# FilterControl_Schematic.net
KiCad netlist of a schematic drawn in Altium Designer
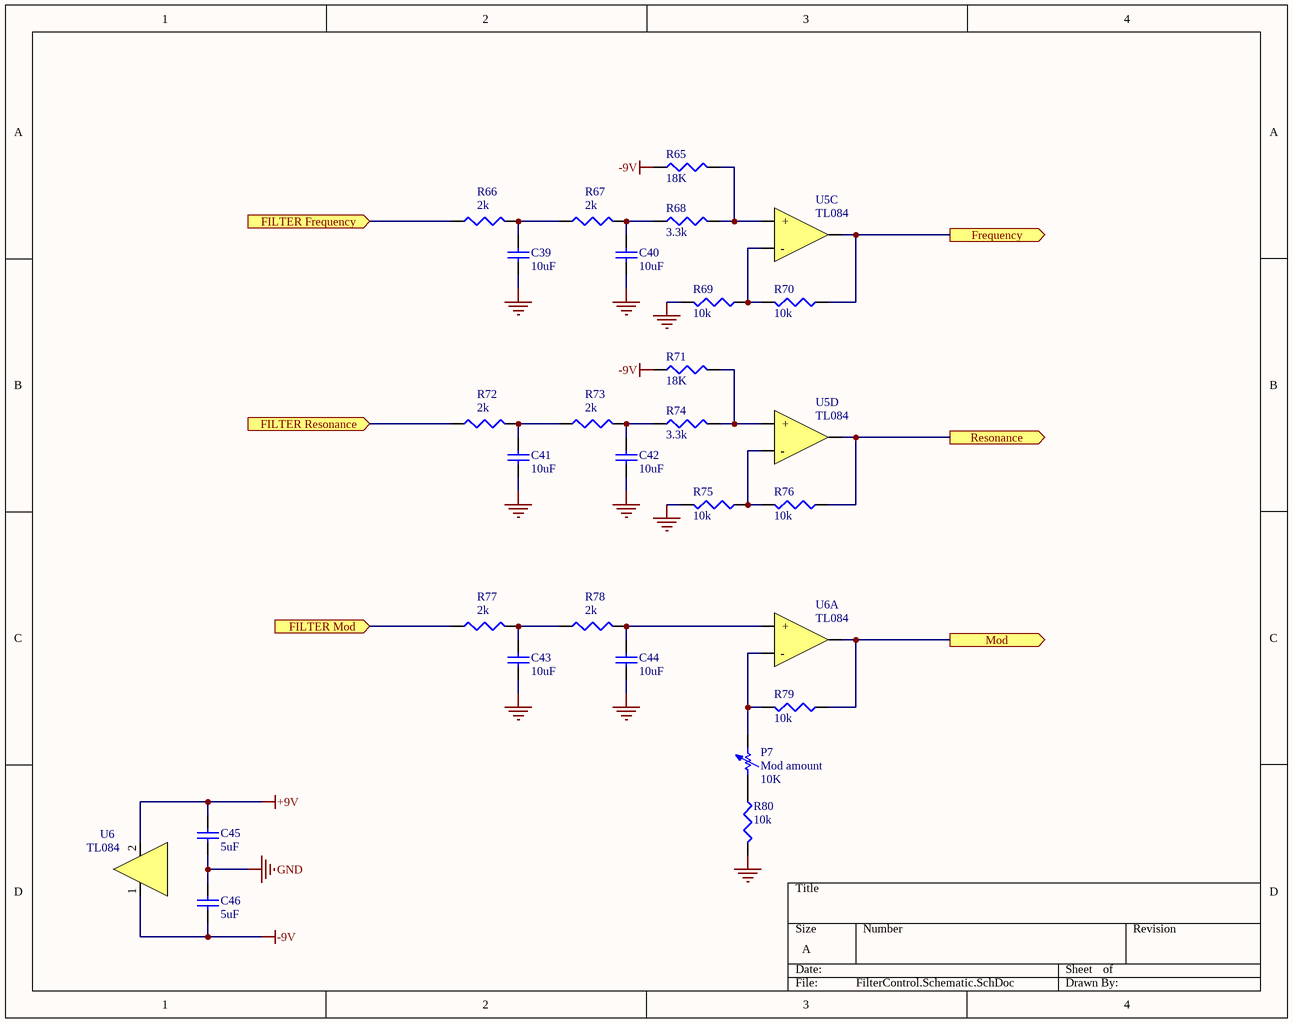
[diagram p0: FilterControl.Schematic.SchDoc]

(export (version "E")
  (design (tool "Eeschema 10.0.6"))
  (components
    (comp (ref "C39")
      (value "10uF")
      (footprint "CAPC1608N - cap")
      (description "Capacitor (Semiconductor SIM Model)")
      (fields (field (name "PUBLISHER") "Altium Limited"))
      (libsource (lib "Miscellaneous Devices") (part "Cap Semi"))
    )
    (comp (ref "C40")
      (value "10uF")
      (footprint "CAPC1608N - cap")
      (description "Capacitor (Semiconductor SIM Model)")
      (fields (field (name "PUBLISHER") "Altium Limited"))
      (libsource (lib "Miscellaneous Devices") (part "Cap Semi"))
    )
    (comp (ref "C41")
      (value "10uF")
      (footprint "CAPC1608N - cap")
      (description "Capacitor (Semiconductor SIM Model)")
      (fields (field (name "PUBLISHER") "Altium Limited"))
      (libsource (lib "Miscellaneous Devices") (part "Cap Semi"))
    )
    (comp (ref "C42")
      (value "10uF")
      (footprint "CAPC1608N - cap")
      (description "Capacitor (Semiconductor SIM Model)")
      (fields (field (name "PUBLISHER") "Altium Limited"))
      (libsource (lib "Miscellaneous Devices") (part "Cap Semi"))
    )
    (comp (ref "C43")
      (value "10uF")
      (footprint "CAPC1608N - cap")
      (description "Capacitor (Semiconductor SIM Model)")
      (fields (field (name "PUBLISHER") "Altium Limited"))
      (libsource (lib "Miscellaneous Devices") (part "Cap Semi"))
    )
    (comp (ref "C44")
      (value "10uF")
      (footprint "CAPC1608N - cap")
      (description "Capacitor (Semiconductor SIM Model)")
      (fields (field (name "PUBLISHER") "Altium Limited"))
      (libsource (lib "Miscellaneous Devices") (part "Cap Semi"))
    )
    (comp (ref "C45")
      (value "5uF")
      (footprint "CAPC1608N - cap")
      (description "Capacitor (Semiconductor SIM Model)")
      (fields (field (name "PUBLISHER") "Altium Limited"))
      (libsource (lib "Miscellaneous Devices") (part "Cap Semi"))
    )
    (comp (ref "C46")
      (value "5uF")
      (footprint "CAPC1608N - cap")
      (description "Capacitor (Semiconductor SIM Model)")
      (fields (field (name "PUBLISHER") "Altium Limited"))
      (libsource (lib "Miscellaneous Devices") (part "Cap Semi"))
    )
    (comp (ref "P7")
      (value "Mod amount")
      (footprint "CAPC1608N")
      (description "Variable Resistor")
      (fields (field (name "ALTIUM_VALUE") "10K") (field (name "PUBLISHER") "Altium Limited"))
      (libsource (lib "Miscellaneous Devices") (part "Res Adj1"))
    )
    (comp (ref "R65")
      (value "18K")
      (footprint "CAPC1608N")
      (description "Resistor")
      (fields (field (name "PUBLISHER") "Altium Limited"))
      (libsource (lib "Miscellaneous Devices") (part "Res3"))
    )
    (comp (ref "R66")
      (value "2k")
      (footprint "CAPC1608N")
      (description "Resistor")
      (fields (field (name "PUBLISHER") "Altium Limited"))
      (libsource (lib "Miscellaneous Devices") (part "Res3"))
    )
    (comp (ref "R67")
      (value "2k")
      (footprint "CAPC1608N")
      (description "Resistor")
      (fields (field (name "PUBLISHER") "Altium Limited"))
      (libsource (lib "Miscellaneous Devices") (part "Res3"))
    )
    (comp (ref "R68")
      (value "3.3k")
      (footprint "CAPC1608N")
      (description "Resistor")
      (fields (field (name "PUBLISHER") "Altium Limited"))
      (libsource (lib "Miscellaneous Devices") (part "Res3"))
    )
    (comp (ref "R69")
      (value "10k")
      (footprint "CAPC1608N")
      (description "Resistor")
      (fields (field (name "PUBLISHER") "Altium Limited"))
      (libsource (lib "Miscellaneous Devices") (part "Res3"))
    )
    (comp (ref "R70")
      (value "10k")
      (footprint "CAPC1608N")
      (description "Resistor")
      (fields (field (name "PUBLISHER") "Altium Limited"))
      (libsource (lib "Miscellaneous Devices") (part "Res3"))
    )
    (comp (ref "R71")
      (value "18K")
      (footprint "CAPC1608N")
      (description "Resistor")
      (fields (field (name "PUBLISHER") "Altium Limited"))
      (libsource (lib "Miscellaneous Devices") (part "Res3"))
    )
    (comp (ref "R72")
      (value "2k")
      (footprint "CAPC1608N")
      (description "Resistor")
      (fields (field (name "PUBLISHER") "Altium Limited"))
      (libsource (lib "Miscellaneous Devices") (part "Res3"))
    )
    (comp (ref "R73")
      (value "2k")
      (footprint "CAPC1608N")
      (description "Resistor")
      (fields (field (name "PUBLISHER") "Altium Limited"))
      (libsource (lib "Miscellaneous Devices") (part "Res3"))
    )
    (comp (ref "R74")
      (value "3.3k")
      (footprint "CAPC1608N")
      (description "Resistor")
      (fields (field (name "PUBLISHER") "Altium Limited"))
      (libsource (lib "Miscellaneous Devices") (part "Res3"))
    )
    (comp (ref "R75")
      (value "10k")
      (footprint "CAPC1608N")
      (description "Resistor")
      (fields (field (name "PUBLISHER") "Altium Limited"))
      (libsource (lib "Miscellaneous Devices") (part "Res3"))
    )
    (comp (ref "R76")
      (value "10k")
      (footprint "CAPC1608N")
      (description "Resistor")
      (fields (field (name "PUBLISHER") "Altium Limited"))
      (libsource (lib "Miscellaneous Devices") (part "Res3"))
    )
    (comp (ref "R77")
      (value "2k")
      (footprint "CAPC1608N")
      (description "Resistor")
      (fields (field (name "PUBLISHER") "Altium Limited"))
      (libsource (lib "Miscellaneous Devices") (part "Res3"))
    )
    (comp (ref "R78")
      (value "2k")
      (footprint "CAPC1608N")
      (description "Resistor")
      (fields (field (name "PUBLISHER") "Altium Limited"))
      (libsource (lib "Miscellaneous Devices") (part "Res3"))
    )
    (comp (ref "R79")
      (value "10k")
      (footprint "CAPC1608N")
      (description "Resistor")
      (fields (field (name "PUBLISHER") "Altium Limited"))
      (libsource (lib "Miscellaneous Devices") (part "Res3"))
    )
    (comp (ref "R80")
      (value "10k")
      (footprint "CAPC1608N")
      (description "Resistor")
      (fields (field (name "PUBLISHER") "Altium Limited"))
      (libsource (lib "Miscellaneous Devices") (part "Res3"))
    )
    (comp (ref "U5C")
      (value "TL084")
      (footprint "TL084 - 3pads")
      (libsource (lib "SynthyTwo.Components") (part "TL084"))
    )
    (comp (ref "U5D")
      (value "TL084")
      (footprint "TL084 - 3pads")
      (libsource (lib "SynthyTwo.Components") (part "TL084"))
    )
    (comp (ref "U6")
      (value "TL084")
      (footprint "TL084 - Alim")
      (libsource (lib "SynthyTwo.Components") (part "TL_CLEAN"))
    )
    (comp (ref "U6A")
      (value "TL084")
      (footprint "TL084 - 3pads")
      (libsource (lib "SynthyTwo.Components") (part "TL084"))
    )
  )
  (nets
    (net (code "1") (name "+9V") (class "Default")
      (node (ref "C45") (pin "1") (pinfunction "1_1") (pintype "passive"))
      (node (ref "U6") (pin "2") (pinfunction "VCC-_2") (pintype "passive"))
    )
    (net (code "2") (name "-9V") (class "Default")
      (node (ref "C46") (pin "2") (pinfunction "2_2") (pintype "passive"))
      (node (ref "R65") (pin "1") (pinfunction "1_1") (pintype "passive"))
      (node (ref "R71") (pin "1") (pinfunction "1_1") (pintype "passive"))
      (node (ref "U6") (pin "1") (pinfunction "VCC+_1") (pintype "passive"))
    )
    (net (code "3") (name "/FILTER Frequency") (class "Default")
      (node (ref "R66") (pin "1") (pinfunction "1_1") (pintype "passive"))
    )
    (net (code "4") (name "/FILTER Mod") (class "Default")
      (node (ref "R77") (pin "1") (pinfunction "1_1") (pintype "passive"))
    )
    (net (code "5") (name "/FILTER Resonance") (class "Default")
      (node (ref "R72") (pin "1") (pinfunction "1_1") (pintype "passive"))
    )
    (net (code "6") (name "/Frequency") (class "Default")
      (node (ref "R70") (pin "1") (pinfunction "1_1") (pintype "passive"))
      (node (ref "U5C") (pin "1") (pinfunction "OUT_1") (pintype "passive"))
    )
    (net (code "7") (name "/Mod") (class "Default")
      (node (ref "R79") (pin "1") (pinfunction "1_1") (pintype "passive"))
      (node (ref "U6A") (pin "1") (pinfunction "OUT_1") (pintype "passive"))
    )
    (net (code "8") (name "/Resonance") (class "Default")
      (node (ref "R76") (pin "1") (pinfunction "1_1") (pintype "passive"))
      (node (ref "U5D") (pin "1") (pinfunction "OUT_1") (pintype "passive"))
    )
    (net (code "9") (name "GND") (class "Default")
      (node (ref "C39") (pin "1") (pinfunction "1_1") (pintype "passive"))
      (node (ref "C40") (pin "1") (pinfunction "1_1") (pintype "passive"))
      (node (ref "C41") (pin "1") (pinfunction "1_1") (pintype "passive"))
      (node (ref "C42") (pin "1") (pinfunction "1_1") (pintype "passive"))
      (node (ref "C43") (pin "1") (pinfunction "1_1") (pintype "passive"))
      (node (ref "C44") (pin "1") (pinfunction "1_1") (pintype "passive"))
      (node (ref "C45") (pin "2") (pinfunction "2_2") (pintype "passive"))
      (node (ref "C46") (pin "1") (pinfunction "1_1") (pintype "passive"))
      (node (ref "R69") (pin "2") (pinfunction "2_2") (pintype "passive"))
      (node (ref "R75") (pin "2") (pinfunction "2_2") (pintype "passive"))
      (node (ref "R80") (pin "2") (pinfunction "2_2") (pintype "passive"))
    )
    (net (code "10") (name "Net-(C39-Pad2)") (class "Default")
      (node (ref "C39") (pin "2") (pinfunction "2_2") (pintype "passive"))
      (node (ref "R66") (pin "2") (pinfunction "2_2") (pintype "passive"))
      (node (ref "R67") (pin "1") (pinfunction "1_1") (pintype "passive"))
    )
    (net (code "11") (name "Net-(C40-Pad2)") (class "Default")
      (node (ref "C40") (pin "2") (pinfunction "2_2") (pintype "passive"))
      (node (ref "R67") (pin "2") (pinfunction "2_2") (pintype "passive"))
      (node (ref "R68") (pin "1") (pinfunction "1_1") (pintype "passive"))
    )
    (net (code "12") (name "Net-(C41-Pad2)") (class "Default")
      (node (ref "C41") (pin "2") (pinfunction "2_2") (pintype "passive"))
      (node (ref "R72") (pin "2") (pinfunction "2_2") (pintype "passive"))
      (node (ref "R73") (pin "1") (pinfunction "1_1") (pintype "passive"))
    )
    (net (code "13") (name "Net-(C42-Pad2)") (class "Default")
      (node (ref "C42") (pin "2") (pinfunction "2_2") (pintype "passive"))
      (node (ref "R73") (pin "2") (pinfunction "2_2") (pintype "passive"))
      (node (ref "R74") (pin "1") (pinfunction "1_1") (pintype "passive"))
    )
    (net (code "14") (name "Net-(C43-Pad2)") (class "Default")
      (node (ref "C43") (pin "2") (pinfunction "2_2") (pintype "passive"))
      (node (ref "R77") (pin "2") (pinfunction "2_2") (pintype "passive"))
      (node (ref "R78") (pin "1") (pinfunction "1_1") (pintype "passive"))
    )
    (net (code "15") (name "Net-(P7-Pad1)") (class "Default")
      (node (ref "P7") (pin "1") (pinfunction "1_1") (pintype "passive"))
      (node (ref "R80") (pin "1") (pinfunction "1_1") (pintype "passive"))
    )
    (net (code "16") (name "Net-(U5C-+)") (class "Default")
      (node (ref "R65") (pin "2") (pinfunction "2_2") (pintype "passive"))
      (node (ref "R68") (pin "2") (pinfunction "2_2") (pintype "passive"))
      (node (ref "U5C") (pin "3") (pinfunction "+_3") (pintype "passive"))
    )
    (net (code "17") (name "Net-(U5C--)") (class "Default")
      (node (ref "R69") (pin "1") (pinfunction "1_1") (pintype "passive"))
      (node (ref "R70") (pin "2") (pinfunction "2_2") (pintype "passive"))
      (node (ref "U5C") (pin "2") (pinfunction "-_2") (pintype "passive"))
    )
    (net (code "18") (name "Net-(U5D-+)") (class "Default")
      (node (ref "R71") (pin "2") (pinfunction "2_2") (pintype "passive"))
      (node (ref "R74") (pin "2") (pinfunction "2_2") (pintype "passive"))
      (node (ref "U5D") (pin "3") (pinfunction "+_3") (pintype "passive"))
    )
    (net (code "19") (name "Net-(U5D--)") (class "Default")
      (node (ref "R75") (pin "1") (pinfunction "1_1") (pintype "passive"))
      (node (ref "R76") (pin "2") (pinfunction "2_2") (pintype "passive"))
      (node (ref "U5D") (pin "2") (pinfunction "-_2") (pintype "passive"))
    )
    (net (code "20") (name "Net-(U6A-+)") (class "Default")
      (node (ref "C44") (pin "2") (pinfunction "2_2") (pintype "passive"))
      (node (ref "R78") (pin "2") (pinfunction "2_2") (pintype "passive"))
      (node (ref "U6A") (pin "3") (pinfunction "+_3") (pintype "passive"))
    )
    (net (code "21") (name "Net-(U6A--)") (class "Default")
      (node (ref "P7") (pin "2") (pinfunction "2_2") (pintype "passive"))
      (node (ref "R79") (pin "2") (pinfunction "2_2") (pintype "passive"))
      (node (ref "U6A") (pin "2") (pinfunction "-_2") (pintype "passive"))
    )
  )
)
